# rcps2keyb_v4.net
KiCad netlist of a schematic drawn in EAGLE
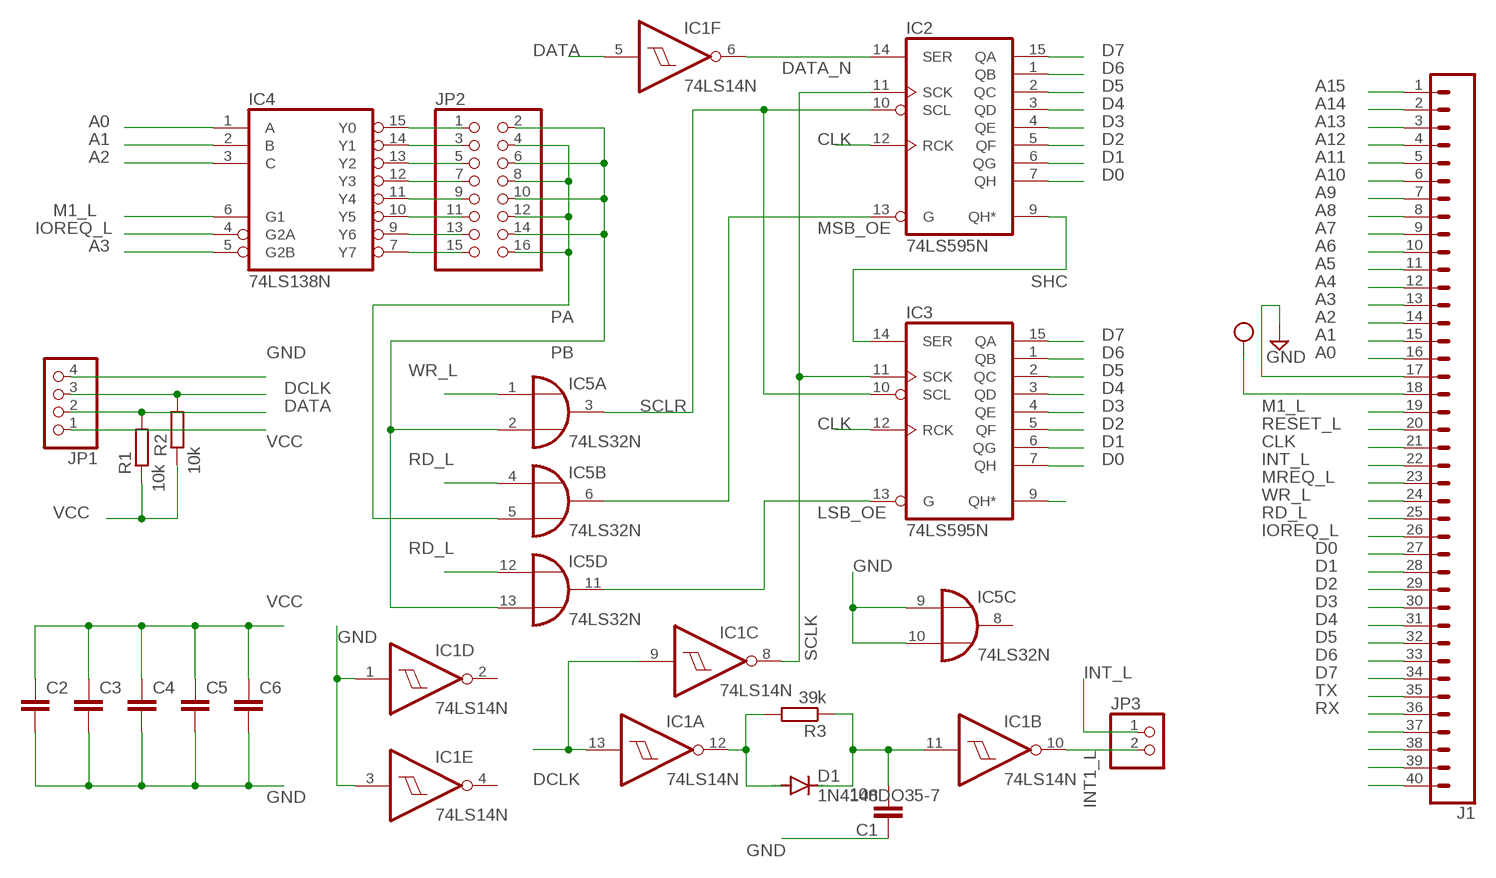
[diagram p0: schematic, sheet 1]

(export (version "E")
  (design (tool "Eeschema 10.0.6"))
  (components
    (comp (ref "C1")
      (value "10n")
      (footprint "eagle-import:C050-025X075")
      (libsource (lib "eagle-import") (part "rcl_334_C-EU050-025X075"))
    )
    (comp (ref "C2")
      (value "C-EU050-025X075")
      (footprint "eagle-import:C050-025X075")
      (libsource (lib "eagle-import") (part "C-EU050-025X075"))
    )
    (comp (ref "C3")
      (value "C-EU050-025X075")
      (footprint "eagle-import:C050-025X075")
      (libsource (lib "eagle-import") (part "C-EU050-025X075"))
    )
    (comp (ref "C4")
      (value "C-EU050-025X075")
      (footprint "eagle-import:C050-025X075")
      (libsource (lib "eagle-import") (part "C-EU050-025X075"))
    )
    (comp (ref "C5")
      (value "C-EU050-025X075")
      (footprint "eagle-import:C050-025X075")
      (libsource (lib "eagle-import") (part "C-EU050-025X075"))
    )
    (comp (ref "C6")
      (value "C-EU050-025X075")
      (footprint "eagle-import:C050-025X075")
      (libsource (lib "eagle-import") (part "C-EU050-025X075"))
    )
    (comp (ref "D1")
      (value "1N4148DO35-7")
      (footprint "eagle-import:DO35-7")
      (libsource (lib "eagle-import") (part "1N4148DO35-7"))
    )
    (comp (ref "IC1")
      (value "74LS14N")
      (footprint "eagle-import:DIL14")
      (libsource (lib "eagle-import") (part "7414NLS"))
    )
    (comp (ref "IC2")
      (value "74LS595N")
      (footprint "eagle-import:DIL16")
      (libsource (lib "eagle-import") (part "74595NLS"))
    )
    (comp (ref "IC3")
      (value "74LS595N")
      (footprint "eagle-import:DIL16")
      (libsource (lib "eagle-import") (part "74595NLS"))
    )
    (comp (ref "IC4")
      (value "74LS138N")
      (footprint "eagle-import:DIL16")
      (libsource (lib "eagle-import") (part "74138NLS"))
    )
    (comp (ref "IC5")
      (value "74LS32N")
      (footprint "eagle-import:DIL14")
      (libsource (lib "eagle-import") (part "7432NLS"))
    )
    (comp (ref "J1")
      (value "CONN_40OFFSET")
      (footprint "eagle-import:1X40_OFFSET")
      (libsource (lib "eagle-import") (part "CONN_40OFFSET"))
    )
    (comp (ref "JP1")
      (value "PINHD-1X4")
      (footprint "eagle-import:1X04")
      (libsource (lib "eagle-import") (part "PINHD-1X4"))
    )
    (comp (ref "JP2")
      (value "PINHD-2X8")
      (footprint "eagle-import:2X08")
      (libsource (lib "eagle-import") (part "PINHD-2X8"))
    )
    (comp (ref "JP3")
      (value "PINHD-1X2")
      (footprint "eagle-import:1X02")
      (libsource (lib "eagle-import") (part "PINHD-1X2"))
    )
    (comp (ref "R1")
      (value "10k")
      (footprint "eagle-import:0204_7")
      (libsource (lib "eagle-import") (part "R-EU_0204/7"))
    )
    (comp (ref "R2")
      (value "10k")
      (footprint "eagle-import:0204_7")
      (libsource (lib "eagle-import") (part "R-EU_0204/7"))
    )
    (comp (ref "R3")
      (value "39k")
      (footprint "eagle-import:0204_7")
      (libsource (lib "eagle-import") (part "R-EU_0204/7"))
    )
  )
  (nets
    (net (code "1") (name "/A0") (class "Default")
      (node (ref "IC4") (pin "1") (pinfunction "A_1") (pintype "input"))
      (node (ref "J1") (pin "16") (pinfunction "16_16") (pintype "passive"))
    )
    (net (code "2") (name "/A1") (class "Default")
      (node (ref "IC4") (pin "2") (pinfunction "B_2") (pintype "input"))
      (node (ref "J1") (pin "15") (pinfunction "15_15") (pintype "passive"))
    )
    (net (code "3") (name "/A2") (class "Default")
      (node (ref "IC4") (pin "3") (pinfunction "C_3") (pintype "input"))
      (node (ref "J1") (pin "14") (pinfunction "14_14") (pintype "passive"))
    )
    (net (code "4") (name "/A3") (class "Default")
      (node (ref "IC4") (pin "5") (pinfunction "G2B_5") (pintype "input"))
      (node (ref "J1") (pin "13") (pinfunction "13_13") (pintype "passive"))
    )
    (net (code "5") (name "/A4") (class "Default")
      (node (ref "J1") (pin "12") (pinfunction "12_12") (pintype "passive"))
    )
    (net (code "6") (name "/A5") (class "Default")
      (node (ref "J1") (pin "11") (pinfunction "11_11") (pintype "passive"))
    )
    (net (code "7") (name "/A6") (class "Default")
      (node (ref "J1") (pin "10") (pinfunction "10_10") (pintype "passive"))
    )
    (net (code "8") (name "/A7") (class "Default")
      (node (ref "J1") (pin "9") (pinfunction "9_9") (pintype "passive"))
    )
    (net (code "9") (name "/A8") (class "Default")
      (node (ref "J1") (pin "8") (pinfunction "8_8") (pintype "passive"))
    )
    (net (code "10") (name "/A9") (class "Default")
      (node (ref "J1") (pin "7") (pinfunction "7_7") (pintype "passive"))
    )
    (net (code "11") (name "/A10") (class "Default")
      (node (ref "J1") (pin "6") (pinfunction "6_6") (pintype "passive"))
    )
    (net (code "12") (name "/A11") (class "Default")
      (node (ref "J1") (pin "5") (pinfunction "5_5") (pintype "passive"))
    )
    (net (code "13") (name "/A12") (class "Default")
      (node (ref "J1") (pin "4") (pinfunction "4_4") (pintype "passive"))
    )
    (net (code "14") (name "/A13") (class "Default")
      (node (ref "J1") (pin "3") (pinfunction "3_3") (pintype "passive"))
    )
    (net (code "15") (name "/A14") (class "Default")
      (node (ref "J1") (pin "2") (pinfunction "2_2") (pintype "passive"))
    )
    (net (code "16") (name "/A15") (class "Default")
      (node (ref "J1") (pin "1") (pinfunction "1_1") (pintype "passive"))
    )
    (net (code "17") (name "/CLK") (class "Default")
      (node (ref "IC2") (pin "12") (pinfunction "RCK_12") (pintype "input"))
      (node (ref "IC3") (pin "12") (pinfunction "RCK_12") (pintype "input"))
      (node (ref "J1") (pin "21") (pinfunction "21_21") (pintype "passive"))
    )
    (net (code "18") (name "/D0") (class "Default")
      (node (ref "IC2") (pin "7") (pinfunction "QH_7") (pintype "tri_state"))
      (node (ref "IC3") (pin "7") (pinfunction "QH_7") (pintype "tri_state"))
      (node (ref "J1") (pin "27") (pinfunction "27_27") (pintype "passive"))
    )
    (net (code "19") (name "/D1") (class "Default")
      (node (ref "IC2") (pin "6") (pinfunction "QG_6") (pintype "tri_state"))
      (node (ref "IC3") (pin "6") (pinfunction "QG_6") (pintype "tri_state"))
      (node (ref "J1") (pin "28") (pinfunction "28_28") (pintype "passive"))
    )
    (net (code "20") (name "/D2") (class "Default")
      (node (ref "IC2") (pin "5") (pinfunction "QF_5") (pintype "tri_state"))
      (node (ref "IC3") (pin "5") (pinfunction "QF_5") (pintype "tri_state"))
      (node (ref "J1") (pin "29") (pinfunction "29_29") (pintype "passive"))
    )
    (net (code "21") (name "/D3") (class "Default")
      (node (ref "IC2") (pin "4") (pinfunction "QE_4") (pintype "tri_state"))
      (node (ref "IC3") (pin "4") (pinfunction "QE_4") (pintype "tri_state"))
      (node (ref "J1") (pin "30") (pinfunction "30_30") (pintype "passive"))
    )
    (net (code "22") (name "/D4") (class "Default")
      (node (ref "IC2") (pin "3") (pinfunction "QD_3") (pintype "tri_state"))
      (node (ref "IC3") (pin "3") (pinfunction "QD_3") (pintype "tri_state"))
      (node (ref "J1") (pin "31") (pinfunction "31_31") (pintype "passive"))
    )
    (net (code "23") (name "/D5") (class "Default")
      (node (ref "IC2") (pin "2") (pinfunction "QC_2") (pintype "tri_state"))
      (node (ref "IC3") (pin "2") (pinfunction "QC_2") (pintype "tri_state"))
      (node (ref "J1") (pin "32") (pinfunction "32_32") (pintype "passive"))
    )
    (net (code "24") (name "/D6") (class "Default")
      (node (ref "IC2") (pin "1") (pinfunction "QB_1") (pintype "tri_state"))
      (node (ref "IC3") (pin "1") (pinfunction "QB_1") (pintype "tri_state"))
      (node (ref "J1") (pin "33") (pinfunction "33_33") (pintype "passive"))
    )
    (net (code "25") (name "/D7") (class "Default")
      (node (ref "IC2") (pin "15") (pinfunction "QA_15") (pintype "tri_state"))
      (node (ref "IC3") (pin "15") (pinfunction "QA_15") (pintype "tri_state"))
      (node (ref "J1") (pin "34") (pinfunction "34_34") (pintype "passive"))
    )
    (net (code "26") (name "/DATA") (class "Default")
      (node (ref "IC1") (pin "5") (pinfunction "I_5") (pintype "input"))
      (node (ref "JP1") (pin "2") (pinfunction "2_2") (pintype "passive"))
      (node (ref "R1") (pin "2") (pinfunction "2_2") (pintype "passive"))
    )
    (net (code "27") (name "/DATA_N") (class "Default")
      (node (ref "IC1") (pin "6") (pinfunction "O_6") (pintype "output"))
      (node (ref "IC2") (pin "14") (pinfunction "SER_14") (pintype "input"))
    )
    (net (code "28") (name "/DCLK") (class "Default")
      (node (ref "IC1") (pin "13") (pinfunction "I_13") (pintype "input"))
      (node (ref "IC1") (pin "9") (pinfunction "I_9") (pintype "input"))
      (node (ref "JP1") (pin "3") (pinfunction "3_3") (pintype "passive"))
      (node (ref "R2") (pin "2") (pinfunction "2_2") (pintype "passive"))
    )
    (net (code "29") (name "/INT1_L") (class "Default")
      (node (ref "IC1") (pin "10") (pinfunction "O_10") (pintype "output"))
      (node (ref "JP3") (pin "2") (pinfunction "2_2") (pintype "passive"))
    )
    (net (code "30") (name "/INT_L") (class "Default")
      (node (ref "J1") (pin "22") (pinfunction "22_22") (pintype "passive"))
      (node (ref "JP3") (pin "1") (pinfunction "1_1") (pintype "passive"))
    )
    (net (code "31") (name "/IOREQ_L") (class "Default")
      (node (ref "IC4") (pin "4") (pinfunction "G2A_4") (pintype "input"))
      (node (ref "J1") (pin "26") (pinfunction "26_26") (pintype "passive"))
    )
    (net (code "32") (name "/LSB_OE") (class "Default")
      (node (ref "IC3") (pin "13") (pinfunction "G_13") (pintype "input"))
      (node (ref "IC5") (pin "11") (pinfunction "O_11") (pintype "output"))
    )
    (net (code "33") (name "/M1_L") (class "Default")
      (node (ref "IC4") (pin "6") (pinfunction "G1_6") (pintype "input"))
      (node (ref "J1") (pin "19") (pinfunction "19_19") (pintype "passive"))
    )
    (net (code "34") (name "/MREQ_L") (class "Default")
      (node (ref "J1") (pin "23") (pinfunction "23_23") (pintype "passive"))
    )
    (net (code "35") (name "/MSB_OE") (class "Default")
      (node (ref "IC2") (pin "13") (pinfunction "G_13") (pintype "input"))
      (node (ref "IC5") (pin "6") (pinfunction "O_6") (pintype "output"))
    )
    (net (code "36") (name "/PA") (class "Default")
      (node (ref "IC5") (pin "5") (pinfunction "I1_5") (pintype "input"))
      (node (ref "JP2") (pin "12") (pinfunction "12_12") (pintype "passive"))
      (node (ref "JP2") (pin "16") (pinfunction "16_16") (pintype "passive"))
      (node (ref "JP2") (pin "4") (pinfunction "4_4") (pintype "passive"))
      (node (ref "JP2") (pin "8") (pinfunction "8_8") (pintype "passive"))
    )
    (net (code "37") (name "/PB") (class "Default")
      (node (ref "IC5") (pin "13") (pinfunction "I1_13") (pintype "input"))
      (node (ref "IC5") (pin "2") (pinfunction "I1_2") (pintype "input"))
      (node (ref "JP2") (pin "10") (pinfunction "10_10") (pintype "passive"))
      (node (ref "JP2") (pin "14") (pinfunction "14_14") (pintype "passive"))
      (node (ref "JP2") (pin "2") (pinfunction "2_2") (pintype "passive"))
      (node (ref "JP2") (pin "6") (pinfunction "6_6") (pintype "passive"))
    )
    (net (code "38") (name "/RD_L") (class "Default")
      (node (ref "IC5") (pin "12") (pinfunction "I0_12") (pintype "input"))
      (node (ref "IC5") (pin "4") (pinfunction "I0_4") (pintype "input"))
      (node (ref "J1") (pin "25") (pinfunction "25_25") (pintype "passive"))
    )
    (net (code "39") (name "/RESET_L") (class "Default")
      (node (ref "J1") (pin "20") (pinfunction "20_20") (pintype "passive"))
    )
    (net (code "40") (name "/RX") (class "Default")
      (node (ref "J1") (pin "36") (pinfunction "36_36") (pintype "passive"))
    )
    (net (code "41") (name "/SCLK") (class "Default")
      (node (ref "IC1") (pin "8") (pinfunction "O_8") (pintype "output"))
      (node (ref "IC2") (pin "11") (pinfunction "SCK_11") (pintype "input"))
      (node (ref "IC3") (pin "11") (pinfunction "SCK_11") (pintype "input"))
    )
    (net (code "42") (name "/SCLR") (class "Default")
      (node (ref "IC2") (pin "10") (pinfunction "SCL_10") (pintype "input"))
      (node (ref "IC3") (pin "10") (pinfunction "SCL_10") (pintype "input"))
      (node (ref "IC5") (pin "3") (pinfunction "O_3") (pintype "output"))
    )
    (net (code "43") (name "/SHC") (class "Default")
      (node (ref "IC2") (pin "9") (pinfunction "QH*_9") (pintype "tri_state"))
      (node (ref "IC3") (pin "14") (pinfunction "SER_14") (pintype "input"))
    )
    (net (code "44") (name "/TX") (class "Default")
      (node (ref "J1") (pin "35") (pinfunction "35_35") (pintype "passive"))
    )
    (net (code "45") (name "/WR_L") (class "Default")
      (node (ref "IC5") (pin "1") (pinfunction "I0_1") (pintype "input"))
      (node (ref "J1") (pin "24") (pinfunction "24_24") (pintype "passive"))
    )
    (net (code "46") (name "GND") (class "Default")
      (node (ref "C1") (pin "1") (pinfunction "1_1") (pintype "passive"))
      (node (ref "C2") (pin "2") (pinfunction "2_2") (pintype "passive"))
      (node (ref "C3") (pin "2") (pinfunction "2_2") (pintype "passive"))
      (node (ref "C4") (pin "2") (pinfunction "2_2") (pintype "passive"))
      (node (ref "C5") (pin "2") (pinfunction "2_2") (pintype "passive"))
      (node (ref "C6") (pin "2") (pinfunction "2_2") (pintype "passive"))
      (node (ref "IC1") (pin "1") (pinfunction "I_1") (pintype "input"))
      (node (ref "IC1") (pin "3") (pinfunction "I_3") (pintype "input"))
      (node (ref "IC5") (pin "10") (pinfunction "I1_10") (pintype "input"))
      (node (ref "IC5") (pin "9") (pinfunction "I0_9") (pintype "input"))
      (node (ref "J1") (pin "17") (pinfunction "17_17") (pintype "passive"))
      (node (ref "JP1") (pin "4") (pinfunction "4_4") (pintype "passive"))
    )
    (net (code "47") (name "Net-(IC1A-O)") (class "Default")
      (node (ref "D1") (pin "A") (pinfunction "A_A") (pintype "passive"))
      (node (ref "IC1") (pin "12") (pinfunction "O_12") (pintype "output"))
      (node (ref "R3") (pin "2") (pinfunction "2_2") (pintype "passive"))
    )
    (net (code "48") (name "Net-(IC1B-I)") (class "Default")
      (node (ref "C1") (pin "2") (pinfunction "2_2") (pintype "passive"))
      (node (ref "D1") (pin "C") (pinfunction "C_C") (pintype "passive"))
      (node (ref "IC1") (pin "11") (pinfunction "I_11") (pintype "input"))
      (node (ref "R3") (pin "1") (pinfunction "1_1") (pintype "passive"))
    )
    (net (code "49") (name "Net-(IC4A-Y0)") (class "Default")
      (node (ref "IC4") (pin "15") (pinfunction "Y0_15") (pintype "output"))
      (node (ref "JP2") (pin "1") (pinfunction "1_1") (pintype "passive"))
    )
    (net (code "50") (name "Net-(IC4A-Y1)") (class "Default")
      (node (ref "IC4") (pin "14") (pinfunction "Y1_14") (pintype "output"))
      (node (ref "JP2") (pin "3") (pinfunction "3_3") (pintype "passive"))
    )
    (net (code "51") (name "Net-(IC4A-Y2)") (class "Default")
      (node (ref "IC4") (pin "13") (pinfunction "Y2_13") (pintype "output"))
      (node (ref "JP2") (pin "5") (pinfunction "5_5") (pintype "passive"))
    )
    (net (code "52") (name "Net-(IC4A-Y3)") (class "Default")
      (node (ref "IC4") (pin "12") (pinfunction "Y3_12") (pintype "output"))
      (node (ref "JP2") (pin "7") (pinfunction "7_7") (pintype "passive"))
    )
    (net (code "53") (name "Net-(IC4A-Y4)") (class "Default")
      (node (ref "IC4") (pin "11") (pinfunction "Y4_11") (pintype "output"))
      (node (ref "JP2") (pin "9") (pinfunction "9_9") (pintype "passive"))
    )
    (net (code "54") (name "Net-(IC4A-Y5)") (class "Default")
      (node (ref "IC4") (pin "10") (pinfunction "Y5_10") (pintype "output"))
      (node (ref "JP2") (pin "11") (pinfunction "11_11") (pintype "passive"))
    )
    (net (code "55") (name "Net-(IC4A-Y6)") (class "Default")
      (node (ref "IC4") (pin "9") (pinfunction "Y6_9") (pintype "output"))
      (node (ref "JP2") (pin "13") (pinfunction "13_13") (pintype "passive"))
    )
    (net (code "56") (name "Net-(IC4A-Y7)") (class "Default")
      (node (ref "IC4") (pin "7") (pinfunction "Y7_7") (pintype "output"))
      (node (ref "JP2") (pin "15") (pinfunction "15_15") (pintype "passive"))
    )
    (net (code "57") (name "VCC") (class "Default")
      (node (ref "C2") (pin "1") (pinfunction "1_1") (pintype "passive"))
      (node (ref "C3") (pin "1") (pinfunction "1_1") (pintype "passive"))
      (node (ref "C4") (pin "1") (pinfunction "1_1") (pintype "passive"))
      (node (ref "C5") (pin "1") (pinfunction "1_1") (pintype "passive"))
      (node (ref "C6") (pin "1") (pinfunction "1_1") (pintype "passive"))
      (node (ref "J1") (pin "18") (pinfunction "18_18") (pintype "passive"))
      (node (ref "JP1") (pin "1") (pinfunction "1_1") (pintype "passive"))
      (node (ref "R1") (pin "1") (pinfunction "1_1") (pintype "passive"))
      (node (ref "R2") (pin "1") (pinfunction "1_1") (pintype "passive"))
    )
    (net (code "58") (name "unconnected-(IC1D-O-Pad2)") (class "Default")
      (node (ref "IC1") (pin "2") (pinfunction "O_2") (pintype "output"))
    )
    (net (code "59") (name "unconnected-(IC1E-O-Pad4)") (class "Default")
      (node (ref "IC1") (pin "4") (pinfunction "O_4") (pintype "output"))
    )
    (net (code "60") (name "unconnected-(IC3A-QH*-Pad9)") (class "Default")
      (node (ref "IC3") (pin "9") (pinfunction "QH*_9") (pintype "tri_state"))
    )
    (net (code "61") (name "unconnected-(IC5C-O-Pad8)") (class "Default")
      (node (ref "IC5") (pin "8") (pinfunction "O_8") (pintype "output"))
    )
    (net (code "62") (name "unconnected-(J1-Pad37)") (class "Default")
      (node (ref "J1") (pin "37") (pinfunction "37_37") (pintype "passive"))
    )
    (net (code "63") (name "unconnected-(J1-Pad38)") (class "Default")
      (node (ref "J1") (pin "38") (pinfunction "38_38") (pintype "passive"))
    )
    (net (code "64") (name "unconnected-(J1-Pad39)") (class "Default")
      (node (ref "J1") (pin "39") (pinfunction "39_39") (pintype "passive"))
    )
    (net (code "65") (name "unconnected-(J1-Pad40)") (class "Default")
      (node (ref "J1") (pin "40") (pinfunction "40_40") (pintype "passive"))
    )
  )
)
